# PWM_Generation.net
KiCad netlist of a schematic drawn in Altium Designer
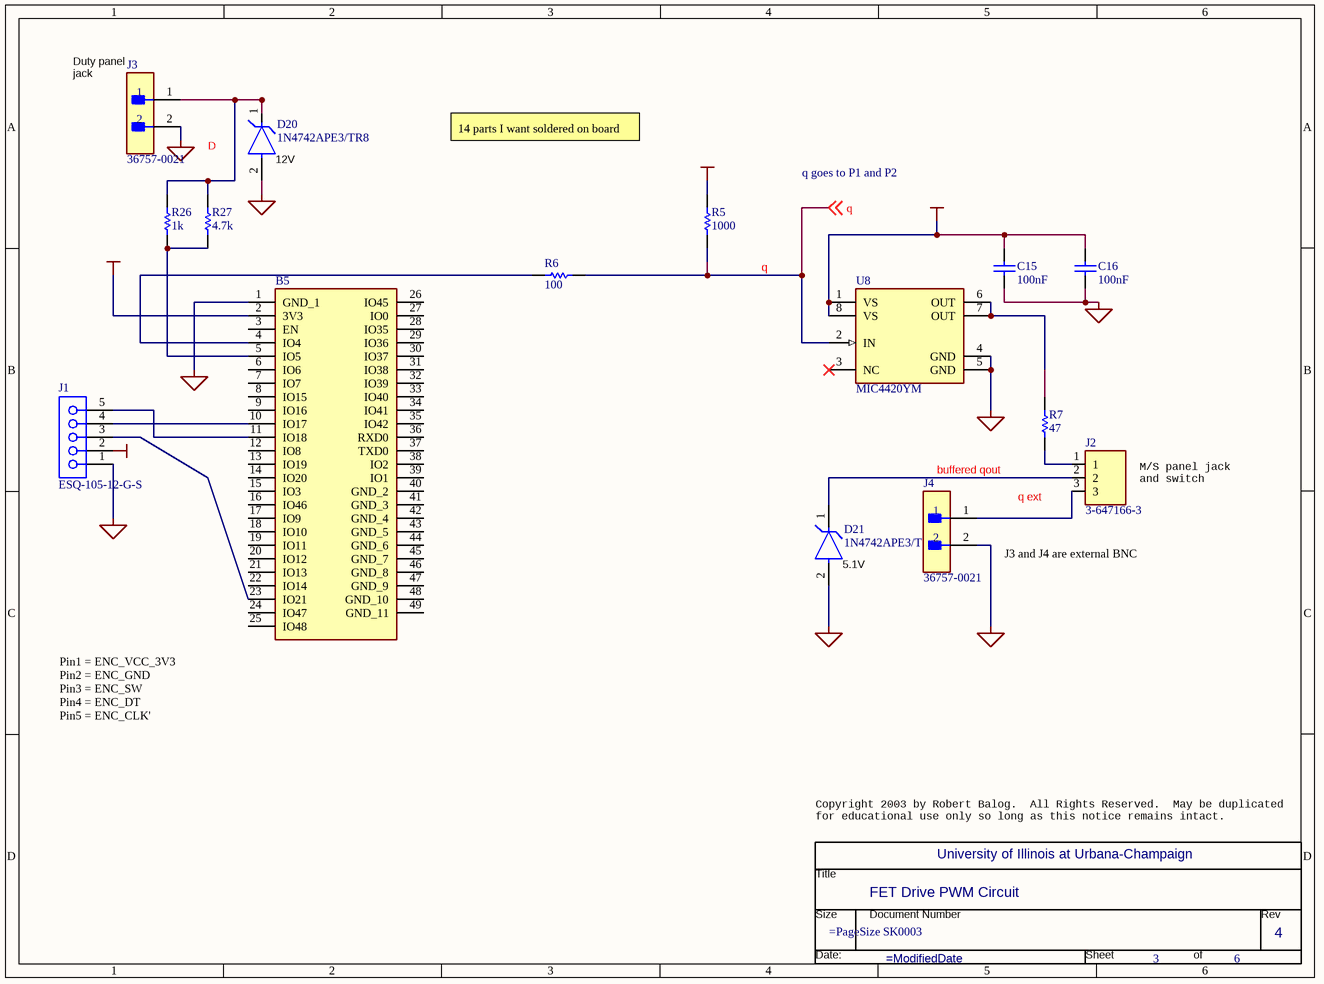
[diagram p0: PWM Generation.SchDoc]

(export (version "E")
  (design (tool "Eeschema 10.0.6"))
  (components
    (comp (ref "*")
      (value "~")
      (fields
        (field (name "PAGE COUNT") "6")
        (field (name "PAGE NUMBER") "3")
        (field (name "TITLE") "FET Drive PWM Circuit")
        (field (name "REVCODE") "4")
        (field (name "DOC") "SK0003")
        (field (name "ORGNAME") "University of Illinois at Urbana-Champaign")
      )
      (libsource (lib "*") (part "TitleBlock0"))
    )
    (comp (ref "B5")
      (value "~")
      (footprint "ESP32S3WROOM1N16R8")
      (fields
        (field (name "MANUFACTURER_PART_NUMBER") "ESP32-S3-WROOM-1-N16R8")
        (field (name "MOUSER PART NUMBER") "356-ESP32S3WRM1N16R8")
      )
      (libsource (lib "ESP32-S3-WROOM-1-N16R8") (part "ESP32-S3-WROOM-1-N16R8"))
    )
    (comp (ref "C15")
      (value "100nF")
      (footprint "CAPC2013X140X50ML20T25")
      (fields
        (field (name "PART NUMBER") "0805DD104KAT2A")
        (field (name "MANUFACTURER") "AVX Interconnect / Elco")
      )
      (libsource (lib "Altium Content Vault") (part "CAP"))
    )
    (comp (ref "C16")
      (value "100nF")
      (footprint "CAPC2013X140X50ML20T25")
      (fields
        (field (name "PART NUMBER") "0805DD104KAT2A")
        (field (name "MANUFACTURER") "AVX Interconnect / Elco")
      )
      (libsource (lib "Altium Content Vault") (part "CAP"))
    )
    (comp (ref "D20")
      (value "1N4742APE3/TR8")
      (footprint "FP-1N4742APE3-TR8-MFG")
      (description "DIODE ZENER 12V 1W DO204AL")
      (libsource (lib "Altium Content Vault") (part "f813f71cba58e380607f5dd3caf9714"))
    )
    (comp (ref "D21")
      (value "1N4742APE3/TR8")
      (footprint "FP-1N4742APE3-TR8-MFG")
      (description "DIODE ZENER 12V 1W DO204AL")
      (libsource (lib "Altium Content Vault") (part "f813f71cba58e380607f5dd3caf9714"))
    )
    (comp (ref "J1")
      (value "ESQ-105-12-G-S")
      (footprint "SMTC-ESQ-105-12-X-S")
      (fields (field (name "MANUFACTURER") "Samtec"))
      (libsource (lib "Altium Content Vault") (part "SMTC-ESQ-105-12-X-S"))
    )
    (comp (ref "J2")
      (value "3-647166-3")
      (footprint "TE_3-647166-3")
      (description "Header Assembly 3P MTA100 SM FL LF MTA-100 Series ¦ TE Connectivity 3-647166-3")
      (fields (field (name "MF") "TE Connectivity"))
      (libsource (lib "3-647166-3") (part "3-647166-3"))
    )
    (comp (ref "J3")
      (value "36757-0021")
      (footprint "FP-36757-0021-MFG")
      (description "CONN HEADER VERT 2POS 6.35MM")
      (libsource (lib "Altium Content Vault") (part "3bc925449376181038e59eaffc5286c"))
    )
    (comp (ref "J4")
      (value "36757-0021")
      (footprint "FP-36757-0021-MFG")
      (description "CONN HEADER VERT 2POS 6.35MM")
      (libsource (lib "Altium Content Vault") (part "3bc925449376181038e59eaffc5286c"))
    )
    (comp (ref "R5")
      (value "1000")
      (footprint "RESC2013X60X35NL10T20")
      (fields (field (name "PART NUMBER") "RC0805FR-1380K6L") (field (name "MANUFACTURER") "Yageo"))
      (libsource (lib "Altium Content Vault") (part "RES"))
    )
    (comp (ref "R6")
      (value "100")
      (footprint "RESC2013X60X35NL10T20")
      (fields (field (name "PART NUMBER") "RC0805FR-1380K6L") (field (name "MANUFACTURER") "Yageo"))
      (libsource (lib "Altium Content Vault") (part "RES"))
    )
    (comp (ref "R7")
      (value "47")
      (footprint "RESC2013X60X35NL10T20")
      (fields (field (name "PART NUMBER") "RC0805FR-1380K6L") (field (name "MANUFACTURER") "Yageo"))
      (libsource (lib "Altium Content Vault") (part "RES"))
    )
    (comp (ref "R26")
      (value "1k")
      (footprint "RESC2013X60X35NL10T20")
      (description "100")
      (fields (field (name "PART NUMBER") "RC0805FR-1380K6L") (field (name "MANUFACTURER") "Yageo"))
      (libsource (lib "Altium Content Vault") (part "RES"))
    )
    (comp (ref "R27")
      (value "4.7k")
      (footprint "RESC2013X60X35NL10T20")
      (description "100")
      (fields (field (name "PART NUMBER") "RC0805FR-1380K6L") (field (name "MANUFACTURER") "Yageo"))
      (libsource (lib "Altium Content Vault") (part "RES"))
    )
    (comp (ref "U8")
      (value "MIC4420YM")
      (footprint "FP-SOICN-8LD-PL-1-IPC_C")
      (description "IC GATE DRVR LOW-SIDE 8SOIC")
      (libsource (lib "Altium Content Vault") (part "59696dd0ae0f4050f2c9023f300317a"))
    )
  )
  (nets
    (net (code "2") (name "/buffered qout") (class "Default")
      (node (ref "D21") (pin "1") (pinfunction "C_1") (pintype "passive"))
      (node (ref "J2") (pin "2") (pinfunction "2_2") (pintype "passive"))
    )
    (net (code "4") (name "3.3V") (class "Default")
      (node (ref "B5") (pin "2") (pinfunction "3V3_2") (pintype "passive"))
      (node (ref "J1") (pin "2") (pinfunction "2_2") (pintype "passive"))
    )
    (net (code "5") (name "5V") (class "Default")
      (node (ref "C15") (pin "2") (pinfunction "2_2") (pintype "passive"))
      (node (ref "C16") (pin "2") (pinfunction "2_2") (pintype "passive"))
      (node (ref "R5") (pin "2") (pinfunction "2_2") (pintype "passive"))
      (node (ref "U8") (pin "1") (pinfunction "VS_1") (pintype "power_in"))
      (node (ref "U8") (pin "8") (pinfunction "VS_8") (pintype "power_in"))
    )
    (net (code "7") (name "GND") (class "Default")
      (node (ref "B5") (pin "1") (pinfunction "GND_1_1") (pintype "passive"))
      (node (ref "C15") (pin "1") (pinfunction "1_1") (pintype "passive"))
      (node (ref "C16") (pin "1") (pinfunction "1_1") (pintype "passive"))
      (node (ref "D20") (pin "2") (pinfunction "A_2") (pintype "passive"))
      (node (ref "D21") (pin "2") (pinfunction "A_2") (pintype "passive"))
      (node (ref "J1") (pin "1") (pinfunction "1_1") (pintype "passive"))
      (node (ref "J3") (pin "2") (pinfunction "2_2") (pintype "passive"))
      (node (ref "J4") (pin "2") (pinfunction "2_2") (pintype "passive"))
      (node (ref "U8") (pin "4") (pinfunction "GND_4") (pintype "power_in"))
      (node (ref "U8") (pin "5") (pinfunction "GND_5") (pintype "power_in"))
    )
    (net (code "8") (name "Net-(B5-IO4)") (class "Default")
      (node (ref "B5") (pin "4") (pinfunction "IO4_4") (pintype "passive"))
      (node (ref "R6") (pin "2") (pinfunction "2_2") (pintype "passive"))
    )
    (net (code "9") (name "Net-(B5-IO5)") (class "Default")
      (node (ref "B5") (pin "5") (pinfunction "IO5_5") (pintype "passive"))
      (node (ref "R26") (pin "2") (pinfunction "2_2") (pintype "passive"))
      (node (ref "R27") (pin "2") (pinfunction "2_2") (pintype "passive"))
    )
    (net (code "10") (name "Net-(B5-IO17)") (class "Default")
      (node (ref "B5") (pin "10") (pinfunction "IO17_10") (pintype "passive"))
      (node (ref "J1") (pin "4") (pinfunction "4_4") (pintype "passive"))
    )
    (net (code "11") (name "Net-(B5-IO18)") (class "Default")
      (node (ref "B5") (pin "11") (pinfunction "IO18_11") (pintype "passive"))
      (node (ref "J1") (pin "5") (pinfunction "5_5") (pintype "passive"))
    )
    (net (code "12") (name "Net-(B5-IO21)") (class "Default")
      (node (ref "B5") (pin "23") (pinfunction "IO21_23") (pintype "passive"))
      (node (ref "J1") (pin "3") (pinfunction "3_3") (pintype "passive"))
    )
    (net (code "13") (name "Net-(D20-C)") (class "Default")
      (node (ref "D20") (pin "1") (pinfunction "C_1") (pintype "passive"))
      (node (ref "J3") (pin "1") (pinfunction "1_1") (pintype "passive"))
      (node (ref "R26") (pin "1") (pinfunction "1_1") (pintype "passive"))
      (node (ref "R27") (pin "1") (pinfunction "1_1") (pintype "passive"))
    )
    (net (code "14") (name "Net-(J2-Pad1)") (class "Default")
      (node (ref "J2") (pin "1") (pinfunction "1_1") (pintype "passive"))
      (node (ref "R7") (pin "1") (pinfunction "1_1") (pintype "passive"))
    )
    (net (code "15") (name "Net-(J2-Pad3)") (class "Default")
      (node (ref "J2") (pin "3") (pinfunction "3_3") (pintype "passive"))
      (node (ref "J4") (pin "1") (pinfunction "1_1") (pintype "passive"))
    )
    (net (code "16") (name "Net-(R7-Pad2)") (class "Default")
      (node (ref "R7") (pin "2") (pinfunction "2_2") (pintype "passive"))
      (node (ref "U8") (pin "6") (pinfunction "OUT_6") (pintype "passive"))
      (node (ref "U8") (pin "7") (pinfunction "OUT_7") (pintype "passive"))
    )
    (net (code "17") (name "q") (class "Default")
      (node (ref "R5") (pin "1") (pinfunction "1_1") (pintype "passive"))
      (node (ref "R6") (pin "1") (pinfunction "1_1") (pintype "passive"))
      (node (ref "U8") (pin "2") (pinfunction "IN_2") (pintype "input"))
    )
    (net (code "18") (name "unconnected-(B5-EN-Pad3)") (class "Default")
      (node (ref "B5") (pin "3") (pinfunction "EN_3") (pintype "passive"))
    )
    (net (code "19") (name "unconnected-(B5-GND_2-Pad40)") (class "Default")
      (node (ref "B5") (pin "40") (pinfunction "GND_2_40") (pintype "passive"))
    )
    (net (code "20") (name "unconnected-(B5-GND_3-Pad41)") (class "Default")
      (node (ref "B5") (pin "41") (pinfunction "GND_3_41") (pintype "passive"))
    )
    (net (code "21") (name "unconnected-(B5-GND_4-Pad42)") (class "Default")
      (node (ref "B5") (pin "42") (pinfunction "GND_4_42") (pintype "passive"))
    )
    (net (code "22") (name "unconnected-(B5-GND_5-Pad43)") (class "Default")
      (node (ref "B5") (pin "43") (pinfunction "GND_5_43") (pintype "passive"))
    )
    (net (code "23") (name "unconnected-(B5-GND_6-Pad44)") (class "Default")
      (node (ref "B5") (pin "44") (pinfunction "GND_6_44") (pintype "passive"))
    )
    (net (code "24") (name "unconnected-(B5-GND_7-Pad45)") (class "Default")
      (node (ref "B5") (pin "45") (pinfunction "GND_7_45") (pintype "passive"))
    )
    (net (code "25") (name "unconnected-(B5-GND_8-Pad46)") (class "Default")
      (node (ref "B5") (pin "46") (pinfunction "GND_8_46") (pintype "passive"))
    )
    (net (code "26") (name "unconnected-(B5-GND_9-Pad47)") (class "Default")
      (node (ref "B5") (pin "47") (pinfunction "GND_9_47") (pintype "passive"))
    )
    (net (code "27") (name "unconnected-(B5-GND_10-Pad48)") (class "Default")
      (node (ref "B5") (pin "48") (pinfunction "GND_10_48") (pintype "passive"))
    )
    (net (code "28") (name "unconnected-(B5-GND_11-Pad49)") (class "Default")
      (node (ref "B5") (pin "49") (pinfunction "GND_11_49") (pintype "passive"))
    )
    (net (code "29") (name "unconnected-(B5-IO0-Pad27)") (class "Default")
      (node (ref "B5") (pin "27") (pinfunction "IO0_27") (pintype "passive"))
    )
    (net (code "30") (name "unconnected-(B5-IO1-Pad39)") (class "Default")
      (node (ref "B5") (pin "39") (pinfunction "IO1_39") (pintype "passive"))
    )
    (net (code "31") (name "unconnected-(B5-IO2-Pad38)") (class "Default")
      (node (ref "B5") (pin "38") (pinfunction "IO2_38") (pintype "passive"))
    )
    (net (code "32") (name "unconnected-(B5-IO3-Pad15)") (class "Default")
      (node (ref "B5") (pin "15") (pinfunction "IO3_15") (pintype "passive"))
    )
    (net (code "33") (name "unconnected-(B5-IO6-Pad6)") (class "Default")
      (node (ref "B5") (pin "6") (pinfunction "IO6_6") (pintype "passive"))
    )
    (net (code "34") (name "unconnected-(B5-IO7-Pad7)") (class "Default")
      (node (ref "B5") (pin "7") (pinfunction "IO7_7") (pintype "passive"))
    )
    (net (code "35") (name "unconnected-(B5-IO8-Pad12)") (class "Default")
      (node (ref "B5") (pin "12") (pinfunction "IO8_12") (pintype "passive"))
    )
    (net (code "36") (name "unconnected-(B5-IO9-Pad17)") (class "Default")
      (node (ref "B5") (pin "17") (pinfunction "IO9_17") (pintype "passive"))
    )
    (net (code "37") (name "unconnected-(B5-IO10-Pad18)") (class "Default")
      (node (ref "B5") (pin "18") (pinfunction "IO10_18") (pintype "passive"))
    )
    (net (code "38") (name "unconnected-(B5-IO11-Pad19)") (class "Default")
      (node (ref "B5") (pin "19") (pinfunction "IO11_19") (pintype "passive"))
    )
    (net (code "39") (name "unconnected-(B5-IO12-Pad20)") (class "Default")
      (node (ref "B5") (pin "20") (pinfunction "IO12_20") (pintype "passive"))
    )
    (net (code "40") (name "unconnected-(B5-IO13-Pad21)") (class "Default")
      (node (ref "B5") (pin "21") (pinfunction "IO13_21") (pintype "passive"))
    )
    (net (code "41") (name "unconnected-(B5-IO14-Pad22)") (class "Default")
      (node (ref "B5") (pin "22") (pinfunction "IO14_22") (pintype "passive"))
    )
    (net (code "42") (name "unconnected-(B5-IO15-Pad8)") (class "Default")
      (node (ref "B5") (pin "8") (pinfunction "IO15_8") (pintype "passive"))
    )
    (net (code "43") (name "unconnected-(B5-IO16-Pad9)") (class "Default")
      (node (ref "B5") (pin "9") (pinfunction "IO16_9") (pintype "passive"))
    )
    (net (code "44") (name "unconnected-(B5-IO19-Pad13)") (class "Default")
      (node (ref "B5") (pin "13") (pinfunction "IO19_13") (pintype "passive"))
    )
    (net (code "45") (name "unconnected-(B5-IO20-Pad14)") (class "Default")
      (node (ref "B5") (pin "14") (pinfunction "IO20_14") (pintype "passive"))
    )
    (net (code "46") (name "unconnected-(B5-IO35-Pad28)") (class "Default")
      (node (ref "B5") (pin "28") (pinfunction "IO35_28") (pintype "passive"))
    )
    (net (code "47") (name "unconnected-(B5-IO36-Pad29)") (class "Default")
      (node (ref "B5") (pin "29") (pinfunction "IO36_29") (pintype "passive"))
    )
    (net (code "48") (name "unconnected-(B5-IO37-Pad30)") (class "Default")
      (node (ref "B5") (pin "30") (pinfunction "IO37_30") (pintype "passive"))
    )
    (net (code "49") (name "unconnected-(B5-IO38-Pad31)") (class "Default")
      (node (ref "B5") (pin "31") (pinfunction "IO38_31") (pintype "passive"))
    )
    (net (code "50") (name "unconnected-(B5-IO39-Pad32)") (class "Default")
      (node (ref "B5") (pin "32") (pinfunction "IO39_32") (pintype "passive"))
    )
    (net (code "51") (name "unconnected-(B5-IO40-Pad33)") (class "Default")
      (node (ref "B5") (pin "33") (pinfunction "IO40_33") (pintype "passive"))
    )
    (net (code "52") (name "unconnected-(B5-IO41-Pad34)") (class "Default")
      (node (ref "B5") (pin "34") (pinfunction "IO41_34") (pintype "passive"))
    )
    (net (code "53") (name "unconnected-(B5-IO42-Pad35)") (class "Default")
      (node (ref "B5") (pin "35") (pinfunction "IO42_35") (pintype "passive"))
    )
    (net (code "54") (name "unconnected-(B5-IO45-Pad26)") (class "Default")
      (node (ref "B5") (pin "26") (pinfunction "IO45_26") (pintype "passive"))
    )
    (net (code "55") (name "unconnected-(B5-IO46-Pad16)") (class "Default")
      (node (ref "B5") (pin "16") (pinfunction "IO46_16") (pintype "passive"))
    )
    (net (code "56") (name "unconnected-(B5-IO47-Pad24)") (class "Default")
      (node (ref "B5") (pin "24") (pinfunction "IO47_24") (pintype "passive"))
    )
    (net (code "57") (name "unconnected-(B5-IO48-Pad25)") (class "Default")
      (node (ref "B5") (pin "25") (pinfunction "IO48_25") (pintype "passive"))
    )
    (net (code "58") (name "unconnected-(B5-RXD0-Pad36)") (class "Default")
      (node (ref "B5") (pin "36") (pinfunction "RXD0_36") (pintype "passive"))
    )
    (net (code "59") (name "unconnected-(B5-TXD0-Pad37)") (class "Default")
      (node (ref "B5") (pin "37") (pinfunction "TXD0_37") (pintype "passive"))
    )
    (net (code "60") (name "unconnected-(U8-NC-Pad3)") (class "Default")
      (node (ref "U8") (pin "3") (pinfunction "NC_3") (pintype "passive+no_connect"))
    )
  )
)
